# wireless_breakout.net
KiCad netlist of a schematic drawn in EAGLE
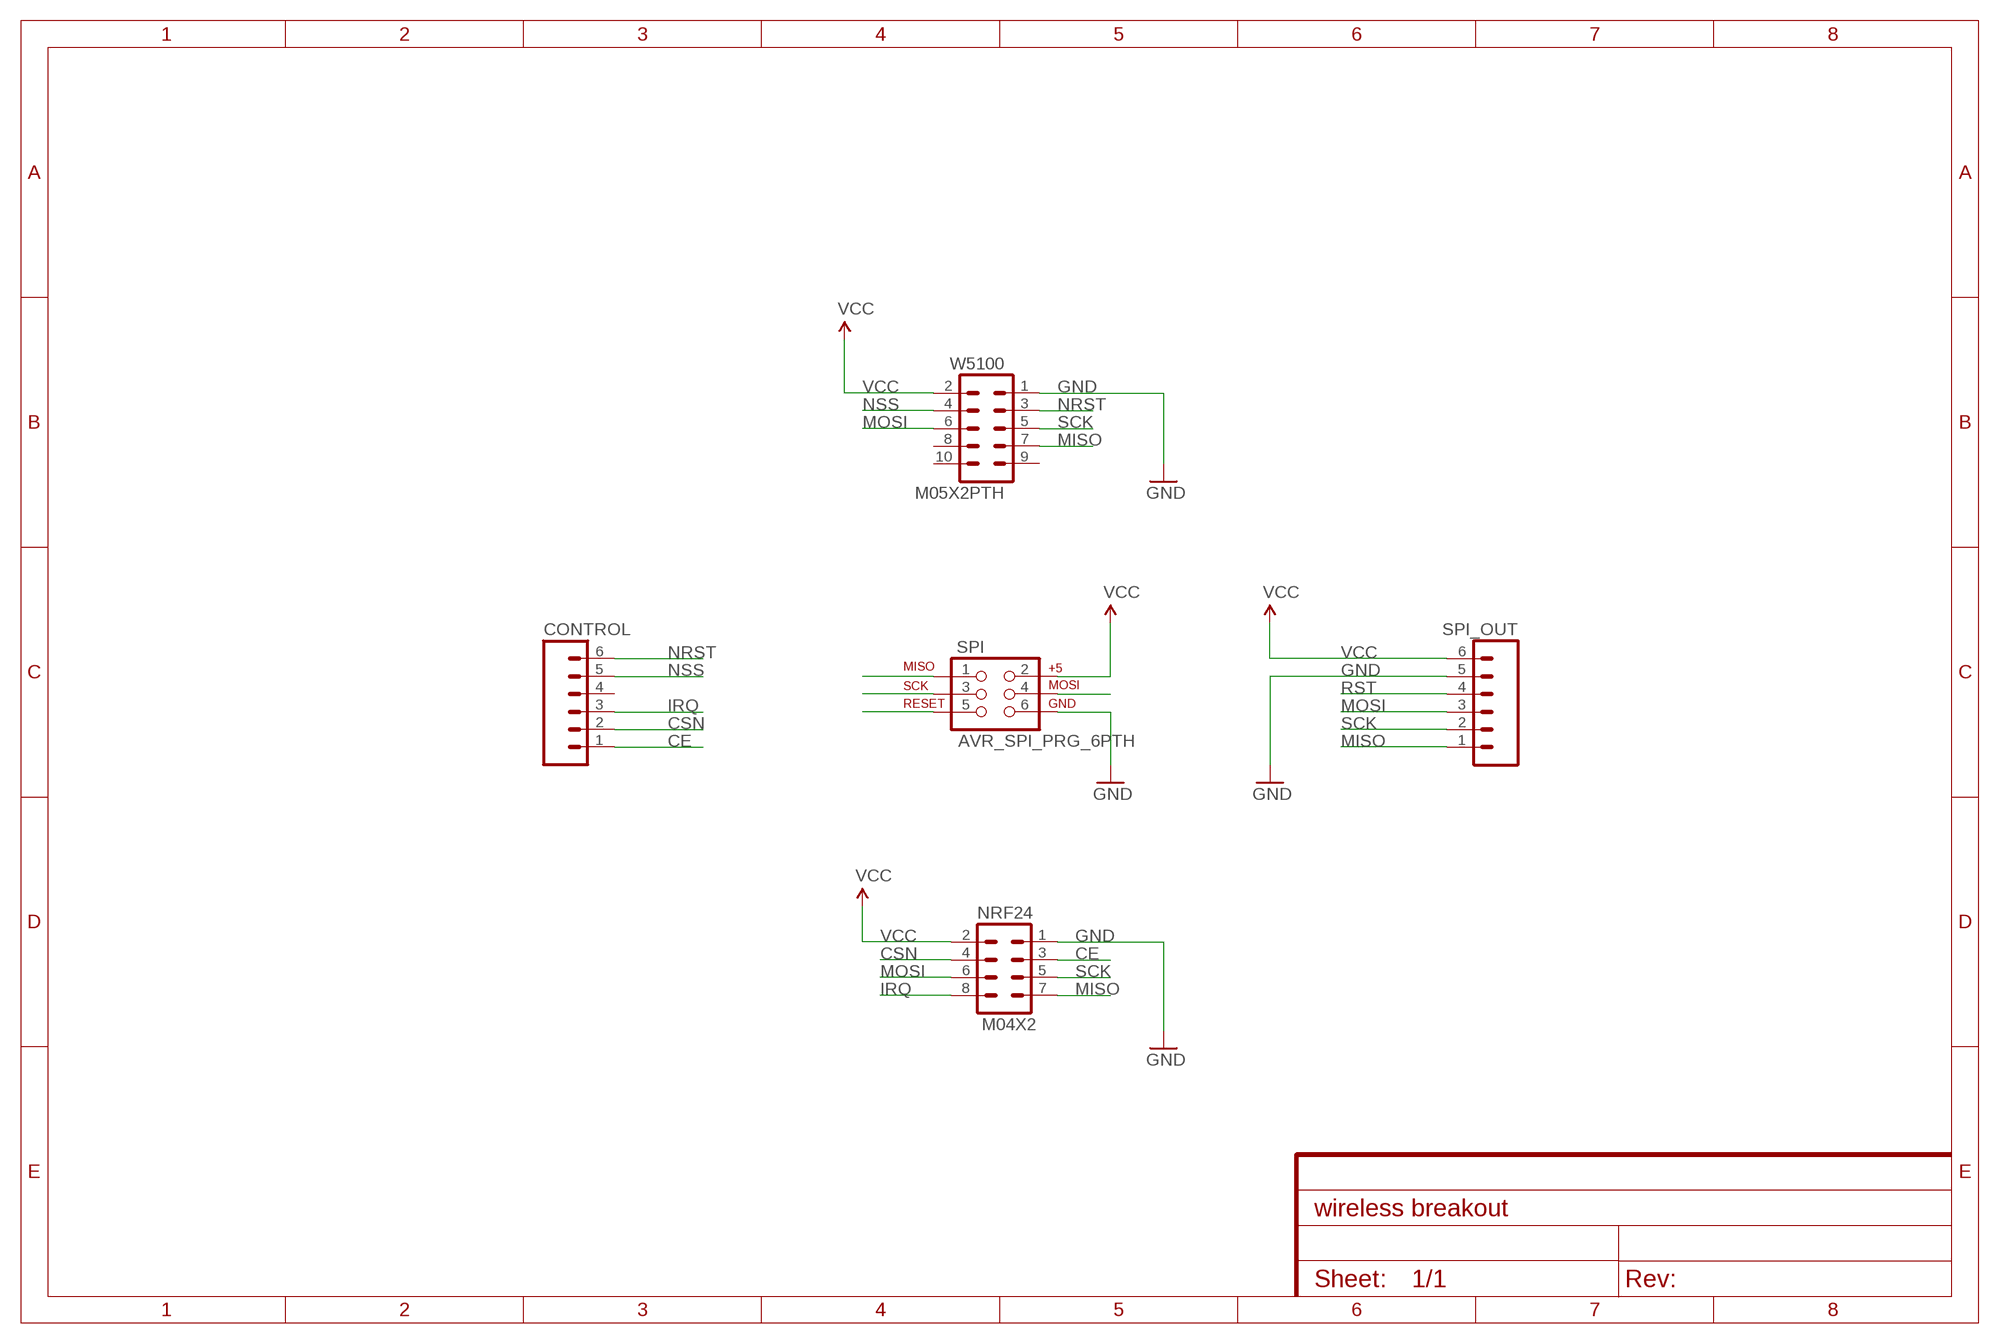
[diagram p0: schematic, sheet 1]

(export (version "E")
  (design (tool "Eeschema 10.0.6"))
  (components
    (comp (ref "CONTROL")
      (value "M06LOCK")
      (footprint "eagle-import:1X06_LOCK")
      (libsource (lib "eagle-import") (part "M06LOCK"))
    )
    (comp (ref "NRF24")
      (value "M04X2")
      (footprint "eagle-import:2X4")
      (libsource (lib "eagle-import") (part "M04X2"))
    )
    (comp (ref "SPI")
      (value "AVR_SPI_PRG_6PTH")
      (footprint "eagle-import:2X3")
      (libsource (lib "eagle-import") (part "AVR_SPI_PRG_6PTH"))
    )
    (comp (ref "SPI_OUT")
      (value "M06LOCK")
      (footprint "eagle-import:1X06_LOCK")
      (libsource (lib "eagle-import") (part "M06LOCK"))
    )
    (comp (ref "W5100")
      (value "M05X2PTH")
      (footprint "eagle-import:AVR_ICSP")
      (libsource (lib "eagle-import") (part "M05X2PTH"))
    )
  )
  (nets
    (net (code "1") (name "/CE") (class "Default")
      (node (ref "CONTROL") (pin "1") (pinfunction "1_1") (pintype "passive"))
      (node (ref "NRF24") (pin "3") (pinfunction "3_3") (pintype "passive"))
    )
    (net (code "2") (name "/CSN") (class "Default")
      (node (ref "CONTROL") (pin "2") (pinfunction "2_2") (pintype "passive"))
      (node (ref "NRF24") (pin "4") (pinfunction "4_4") (pintype "passive"))
    )
    (net (code "3") (name "/IRQ") (class "Default")
      (node (ref "CONTROL") (pin "3") (pinfunction "3_3") (pintype "passive"))
      (node (ref "NRF24") (pin "8") (pinfunction "8_8") (pintype "passive"))
    )
    (net (code "4") (name "/MISO") (class "Default")
      (node (ref "NRF24") (pin "7") (pinfunction "7_7") (pintype "passive"))
      (node (ref "SPI") (pin "1") (pinfunction "1_1") (pintype "passive"))
      (node (ref "SPI_OUT") (pin "1") (pinfunction "1_1") (pintype "passive"))
      (node (ref "W5100") (pin "7") (pinfunction "7_7") (pintype "passive"))
    )
    (net (code "5") (name "/MOSI") (class "Default")
      (node (ref "NRF24") (pin "6") (pinfunction "6_6") (pintype "passive"))
      (node (ref "SPI") (pin "4") (pinfunction "4_4") (pintype "passive"))
      (node (ref "SPI_OUT") (pin "3") (pinfunction "3_3") (pintype "passive"))
      (node (ref "W5100") (pin "6") (pinfunction "6_6") (pintype "passive"))
    )
    (net (code "6") (name "/NRST") (class "Default")
      (node (ref "CONTROL") (pin "6") (pinfunction "6_6") (pintype "passive"))
      (node (ref "W5100") (pin "3") (pinfunction "3_3") (pintype "passive"))
    )
    (net (code "7") (name "/NSS") (class "Default")
      (node (ref "CONTROL") (pin "5") (pinfunction "5_5") (pintype "passive"))
      (node (ref "W5100") (pin "4") (pinfunction "4_4") (pintype "passive"))
    )
    (net (code "8") (name "/RST") (class "Default")
      (node (ref "SPI") (pin "5") (pinfunction "5_5") (pintype "passive"))
      (node (ref "SPI_OUT") (pin "4") (pinfunction "4_4") (pintype "passive"))
    )
    (net (code "9") (name "/SCK") (class "Default")
      (node (ref "NRF24") (pin "5") (pinfunction "5_5") (pintype "passive"))
      (node (ref "SPI") (pin "3") (pinfunction "3_3") (pintype "passive"))
      (node (ref "SPI_OUT") (pin "2") (pinfunction "2_2") (pintype "passive"))
      (node (ref "W5100") (pin "5") (pinfunction "5_5") (pintype "passive"))
    )
    (net (code "10") (name "GND") (class "Default")
      (node (ref "NRF24") (pin "1") (pinfunction "1_1") (pintype "passive"))
      (node (ref "SPI") (pin "6") (pinfunction "6_6") (pintype "passive"))
      (node (ref "SPI_OUT") (pin "5") (pinfunction "5_5") (pintype "passive"))
      (node (ref "W5100") (pin "1") (pinfunction "1_1") (pintype "passive"))
    )
    (net (code "11") (name "VCC") (class "Default")
      (node (ref "NRF24") (pin "2") (pinfunction "2_2") (pintype "passive"))
      (node (ref "SPI") (pin "2") (pinfunction "2_2") (pintype "passive"))
      (node (ref "SPI_OUT") (pin "6") (pinfunction "6_6") (pintype "passive"))
      (node (ref "W5100") (pin "2") (pinfunction "2_2") (pintype "passive"))
    )
    (net (code "12") (name "unconnected-(CONTROL-Pad4)") (class "Default")
      (node (ref "CONTROL") (pin "4") (pinfunction "4_4") (pintype "passive"))
    )
    (net (code "13") (name "unconnected-(W5100-Pad8)") (class "Default")
      (node (ref "W5100") (pin "8") (pinfunction "8_8") (pintype "passive"))
    )
    (net (code "14") (name "unconnected-(W5100-Pad9)") (class "Default")
      (node (ref "W5100") (pin "9") (pinfunction "9_9") (pintype "passive"))
    )
    (net (code "15") (name "unconnected-(W5100-Pad10)") (class "Default")
      (node (ref "W5100") (pin "10") (pinfunction "10_10") (pintype "passive"))
    )
  )
)
